# EM4100_cloner-revB.net
KiCad netlist of a schematic drawn in EAGLE
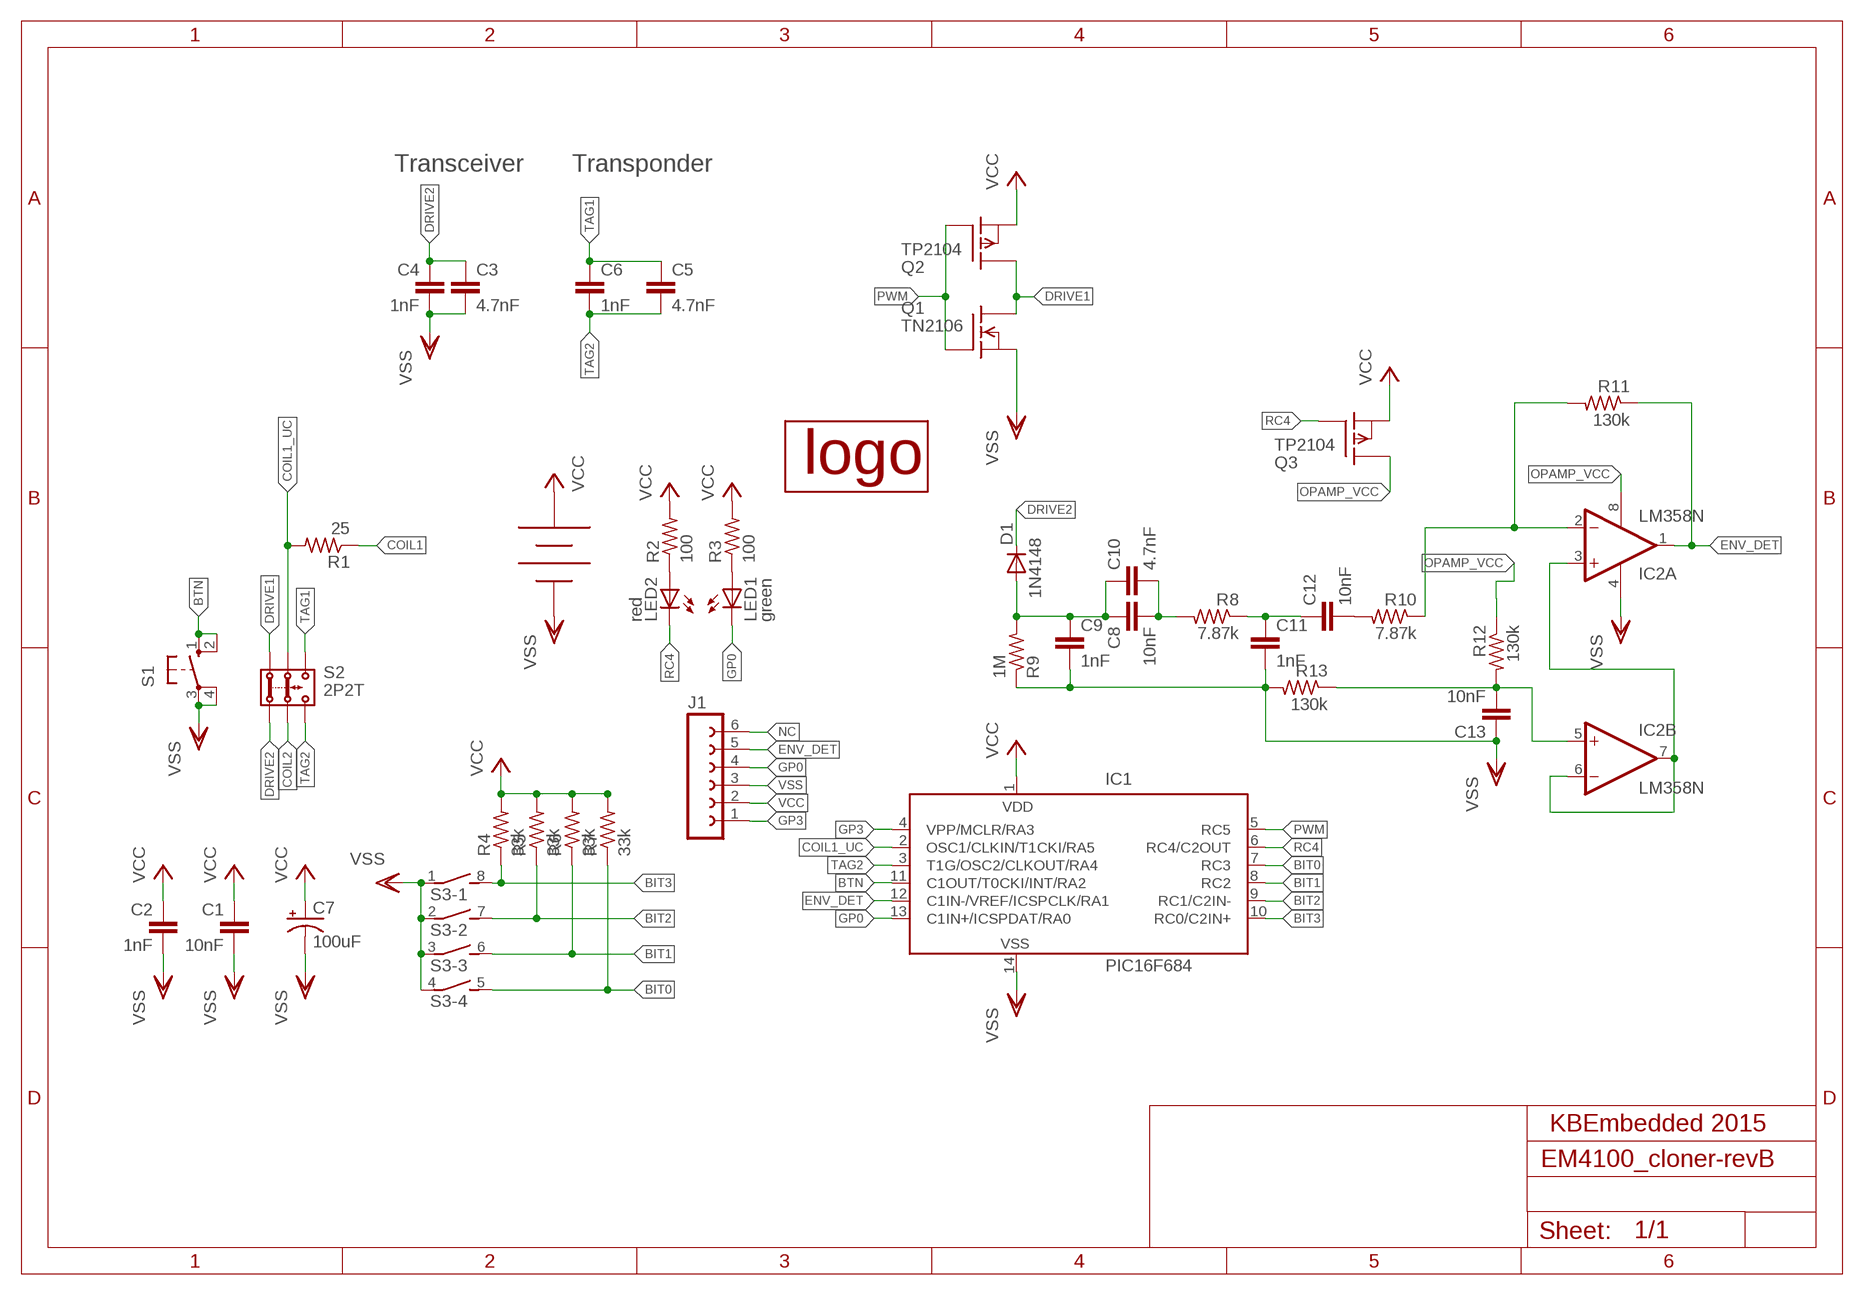
[diagram p0: schematic, sheet 1]

(export (version "E")
  (design (tool "Eeschema 10.0.6"))
  (components
    (comp (ref "BT1")
      (value "BAT-HLD-001-THM")
      (footprint "eagle-import:BAT-HLD-001-THM")
      (libsource (lib "eagle-import") (part "BAT-HLD-001-THM"))
    )
    (comp (ref "C1")
      (value "10nF")
      (footprint "eagle-import:C050-024X044")
      (libsource (lib "eagle-import") (part "C-EU050-024X044"))
    )
    (comp (ref "C2")
      (value "1nF")
      (footprint "eagle-import:C050-024X044")
      (libsource (lib "eagle-import") (part "C-EU050-024X044"))
    )
    (comp (ref "C3")
      (value "4.7nF")
      (footprint "eagle-import:C050-024X044")
      (libsource (lib "eagle-import") (part "C-EU050-024X044"))
    )
    (comp (ref "C4")
      (value "1nF")
      (footprint "eagle-import:C050-024X044")
      (libsource (lib "eagle-import") (part "C-EU050-024X044"))
    )
    (comp (ref "C5")
      (value "4.7nF")
      (footprint "eagle-import:C050-024X044")
      (libsource (lib "eagle-import") (part "C-EU050-024X044"))
    )
    (comp (ref "C6")
      (value "1nF")
      (footprint "eagle-import:C050-024X044")
      (libsource (lib "eagle-import") (part "C-EU050-024X044"))
    )
    (comp (ref "C7")
      (value "100uF")
      (footprint "eagle-import:E2,5-6E")
      (libsource (lib "eagle-import") (part "CPOL-USE2,5-6E"))
    )
    (comp (ref "C8")
      (value "10nF")
      (footprint "eagle-import:C050-024X044")
      (libsource (lib "eagle-import") (part "C-EU050-024X044"))
    )
    (comp (ref "C9")
      (value "1nF")
      (footprint "eagle-import:C050-024X044")
      (libsource (lib "eagle-import") (part "C-EU050-024X044"))
    )
    (comp (ref "C10")
      (value "4.7nF")
      (footprint "eagle-import:C050-024X044")
      (libsource (lib "eagle-import") (part "C-EU050-024X044"))
    )
    (comp (ref "C11")
      (value "1nF")
      (footprint "eagle-import:C050-024X044")
      (libsource (lib "eagle-import") (part "C-EU050-024X044"))
    )
    (comp (ref "C12")
      (value "10nF")
      (footprint "eagle-import:C050-024X044")
      (libsource (lib "eagle-import") (part "C-EU050-024X044"))
    )
    (comp (ref "C13")
      (value "10nF")
      (footprint "eagle-import:C050-024X044")
      (libsource (lib "eagle-import") (part "C-EU050-024X044"))
    )
    (comp (ref "D1")
      (value "1N4148")
      (footprint "eagle-import:D-5")
      (libsource (lib "eagle-import") (part "DIODE-D-5"))
    )
    (comp (ref "IC1")
      (value "PIC16F684")
      (footprint "eagle-import:DIL14")
      (fields (field (name "MF") "MICROCHIP") (field (name "MPN") "PIC16F636-I/P"))
      (libsource (lib "eagle-import") (part "PIC16F636P"))
    )
    (comp (ref "IC2")
      (value "LM358N")
      (footprint "eagle-import:DIL08")
      (libsource (lib "eagle-import") (part "LM358N"))
    )
    (comp (ref "J1")
      (value "FE06-1")
      (footprint "eagle-import:FE06")
      (libsource (lib "eagle-import") (part "FE06-1"))
    )
    (comp (ref "LED1")
      (value "green")
      (footprint "eagle-import:LED3MM")
      (libsource (lib "eagle-import") (part "LED3MM"))
    )
    (comp (ref "LED2")
      (value "red")
      (footprint "eagle-import:LED3MM")
      (libsource (lib "eagle-import") (part "LED3MM"))
    )
    (comp (ref "Q1")
      (value "TN2106")
      (footprint "eagle-import:TO-92")
      (libsource (lib "eagle-import") (part "TN0602N3"))
    )
    (comp (ref "Q2")
      (value "TP2104")
      (footprint "eagle-import:TO-92")
      (libsource (lib "eagle-import") (part "TP0602N3"))
    )
    (comp (ref "Q3")
      (value "TP2104")
      (footprint "eagle-import:TO-92")
      (libsource (lib "eagle-import") (part "TP0602N3"))
    )
    (comp (ref "R1")
      (value "25")
      (footprint "eagle-import:0204_7")
      (libsource (lib "eagle-import") (part "R-US_0204/7"))
    )
    (comp (ref "R2")
      (value "100")
      (footprint "eagle-import:0204_7")
      (libsource (lib "eagle-import") (part "R-US_0204/7"))
    )
    (comp (ref "R3")
      (value "100")
      (footprint "eagle-import:0204_7")
      (libsource (lib "eagle-import") (part "R-US_0204/7"))
    )
    (comp (ref "R4")
      (value "33k")
      (footprint "eagle-import:0204_7")
      (libsource (lib "eagle-import") (part "R-US_0204/7"))
    )
    (comp (ref "R5")
      (value "33k")
      (footprint "eagle-import:0204_7")
      (libsource (lib "eagle-import") (part "R-US_0204/7"))
    )
    (comp (ref "R6")
      (value "33k")
      (footprint "eagle-import:0204_7")
      (libsource (lib "eagle-import") (part "R-US_0204/7"))
    )
    (comp (ref "R7")
      (value "33k")
      (footprint "eagle-import:0204_7")
      (libsource (lib "eagle-import") (part "R-US_0204/7"))
    )
    (comp (ref "R8")
      (value "7.87k")
      (footprint "eagle-import:0204_7")
      (libsource (lib "eagle-import") (part "R-US_0204/7"))
    )
    (comp (ref "R9")
      (value "1M")
      (footprint "eagle-import:0204_7")
      (libsource (lib "eagle-import") (part "R-US_0204/7"))
    )
    (comp (ref "R10")
      (value "7.87k")
      (footprint "eagle-import:0204_7")
      (libsource (lib "eagle-import") (part "R-US_0204/7"))
    )
    (comp (ref "R11")
      (value "130k")
      (footprint "eagle-import:0204_7")
      (libsource (lib "eagle-import") (part "R-US_0204/7"))
    )
    (comp (ref "R12")
      (value "130k")
      (footprint "eagle-import:0204_7")
      (libsource (lib "eagle-import") (part "R-US_0204/7"))
    )
    (comp (ref "R13")
      (value "130k")
      (footprint "eagle-import:0204_7")
      (libsource (lib "eagle-import") (part "R-US_0204/7"))
    )
    (comp (ref "S1")
      (value "10-XX")
      (footprint "eagle-import:B3F-10XX")
      (fields (field (name "MPN") "B3F-1000"))
      (libsource (lib "eagle-import") (part "10-XX"))
    )
    (comp (ref "S2")
      (value "2P2T")
      (footprint "eagle-import:2P2T")
      (libsource (lib "eagle-import") (part "2P2T"))
    )
    (comp (ref "S3")
      (value "DIP04S")
      (footprint "eagle-import:DIP04S")
      (libsource (lib "eagle-import") (part "DIP04S"))
    )
    (comp (ref "U$1")
      (value "KBELOGO-SILK")
      (footprint "eagle-import:KBELOGO-SILK")
      (libsource (lib "eagle-import") (part "KBELOGO-SILK"))
    )
  )
  (nets
    (net (code "1") (name "BIT0") (class "Default")
      (node (ref "IC1") (pin "7") (pinfunction "RC3_7") (pintype "bidirectional"))
      (node (ref "R7") (pin "1") (pinfunction "1_1") (pintype "passive"))
      (node (ref "S3") (pin "5") (pinfunction "2_5") (pintype "passive"))
    )
    (net (code "2") (name "BIT1") (class "Default")
      (node (ref "IC1") (pin "8") (pinfunction "RC2_8") (pintype "bidirectional"))
      (node (ref "R6") (pin "1") (pinfunction "1_1") (pintype "passive"))
      (node (ref "S3") (pin "6") (pinfunction "2_6") (pintype "passive"))
    )
    (net (code "3") (name "BIT2") (class "Default")
      (node (ref "IC1") (pin "9") (pinfunction "RC1/C2IN-_9") (pintype "bidirectional"))
      (node (ref "R5") (pin "1") (pinfunction "1_1") (pintype "passive"))
      (node (ref "S3") (pin "7") (pinfunction "2_7") (pintype "passive"))
    )
    (net (code "4") (name "BIT3") (class "Default")
      (node (ref "IC1") (pin "10") (pinfunction "RC0/C2IN+_10") (pintype "bidirectional"))
      (node (ref "R4") (pin "1") (pinfunction "1_1") (pintype "passive"))
      (node (ref "S3") (pin "8") (pinfunction "2_8") (pintype "passive"))
    )
    (net (code "5") (name "BTN") (class "Default")
      (node (ref "IC1") (pin "11") (pinfunction "C1OUT/T0CKI/INT/RA2_11") (pintype "bidirectional"))
      (node (ref "S1") (pin "1") (pinfunction "S_1") (pintype "passive"))
      (node (ref "S1") (pin "2") (pinfunction "S1_2") (pintype "passive"))
    )
    (net (code "6") (name "COIL1") (class "Default")
      (node (ref "R1") (pin "1") (pinfunction "1_1") (pintype "passive"))
    )
    (net (code "7") (name "COIL1_UC") (class "Default")
      (node (ref "IC1") (pin "2") (pinfunction "OSC1/CLKIN/T1CKI/RA5_2") (pintype "bidirectional"))
      (node (ref "R1") (pin "2") (pinfunction "2_2") (pintype "passive"))
      (node (ref "S2") (pin "2.1") (pinfunction "2.1_2.1") (pintype "passive"))
    )
    (net (code "8") (name "COIL2") (class "Default")
      (node (ref "S2") (pin "2.2") (pinfunction "2.2_2.2") (pintype "passive"))
    )
    (net (code "9") (name "DRIVE1") (class "Default")
      (node (ref "Q1") (pin "3") (pinfunction "D_3") (pintype "passive"))
      (node (ref "Q2") (pin "3") (pinfunction "D_3") (pintype "passive"))
      (node (ref "S2") (pin "1.1") (pinfunction "1.1_1.1") (pintype "passive"))
    )
    (net (code "10") (name "DRIVE2") (class "Default")
      (node (ref "C3") (pin "1") (pinfunction "1_1") (pintype "passive"))
      (node (ref "C4") (pin "1") (pinfunction "1_1") (pintype "passive"))
      (node (ref "D1") (pin "C") (pinfunction "C_C") (pintype "passive"))
      (node (ref "S2") (pin "1.2") (pinfunction "1.2_1.2") (pintype "passive"))
    )
    (net (code "11") (name "ENV_DET") (class "Default")
      (node (ref "IC1") (pin "12") (pinfunction "C1IN-/VREF/ICSPCLK/RA1_12") (pintype "bidirectional"))
      (node (ref "IC2") (pin "1") (pinfunction "OUT_1") (pintype "output"))
      (node (ref "J1") (pin "5") (pinfunction "5_5") (pintype "passive"))
      (node (ref "R11") (pin "1") (pinfunction "1_1") (pintype "passive"))
    )
    (net (code "12") (name "GP0") (class "Default")
      (node (ref "IC1") (pin "13") (pinfunction "C1IN+/ICSPDAT/RA0_13") (pintype "bidirectional"))
      (node (ref "J1") (pin "4") (pinfunction "4_4") (pintype "passive"))
      (node (ref "LED1") (pin "K") (pinfunction "C_K") (pintype "passive"))
    )
    (net (code "13") (name "GP3") (class "Default")
      (node (ref "IC1") (pin "4") (pinfunction "VPP/MCLR/RA3_4") (pintype "input"))
      (node (ref "J1") (pin "1") (pinfunction "1_1") (pintype "passive"))
    )
    (net (code "14") (name "NC") (class "Default")
      (node (ref "J1") (pin "6") (pinfunction "6_6") (pintype "passive"))
    )
    (net (code "15") (name "Net-(C10-Pad1)") (class "Default")
      (node (ref "C10") (pin "1") (pinfunction "1_1") (pintype "passive"))
      (node (ref "C8") (pin "1") (pinfunction "1_1") (pintype "passive"))
      (node (ref "C9") (pin "1") (pinfunction "1_1") (pintype "passive"))
      (node (ref "D1") (pin "A") (pinfunction "A_A") (pintype "passive"))
      (node (ref "R9") (pin "2") (pinfunction "2_2") (pintype "passive"))
    )
    (net (code "16") (name "Net-(C10-Pad2)") (class "Default")
      (node (ref "C10") (pin "2") (pinfunction "2_2") (pintype "passive"))
      (node (ref "C8") (pin "2") (pinfunction "2_2") (pintype "passive"))
      (node (ref "R8") (pin "2") (pinfunction "2_2") (pintype "passive"))
    )
    (net (code "17") (name "Net-(C11-Pad1)") (class "Default")
      (node (ref "C11") (pin "1") (pinfunction "1_1") (pintype "passive"))
      (node (ref "C12") (pin "1") (pinfunction "1_1") (pintype "passive"))
      (node (ref "R8") (pin "1") (pinfunction "1_1") (pintype "passive"))
    )
    (net (code "18") (name "Net-(C12-Pad2)") (class "Default")
      (node (ref "C12") (pin "2") (pinfunction "2_2") (pintype "passive"))
      (node (ref "R10") (pin "2") (pinfunction "2_2") (pintype "passive"))
    )
    (net (code "19") (name "Net-(IC2A-+IN)") (class "Default")
      (node (ref "IC2") (pin "3") (pinfunction "+IN_3") (pintype "input"))
      (node (ref "IC2") (pin "6") (pinfunction "-IN_6") (pintype "input"))
      (node (ref "IC2") (pin "7") (pinfunction "OUT_7") (pintype "output"))
    )
    (net (code "20") (name "Net-(IC2A--IN)") (class "Default")
      (node (ref "IC2") (pin "2") (pinfunction "-IN_2") (pintype "input"))
      (node (ref "R10") (pin "1") (pinfunction "1_1") (pintype "passive"))
      (node (ref "R11") (pin "2") (pinfunction "2_2") (pintype "passive"))
    )
    (net (code "21") (name "Net-(IC2B-+IN)") (class "Default")
      (node (ref "C13") (pin "2") (pinfunction "2_2") (pintype "passive"))
      (node (ref "IC2") (pin "5") (pinfunction "+IN_5") (pintype "input"))
      (node (ref "R12") (pin "2") (pinfunction "2_2") (pintype "passive"))
      (node (ref "R13") (pin "1") (pinfunction "1_1") (pintype "passive"))
    )
    (net (code "22") (name "Net-(LED1-PadA)") (class "Default")
      (node (ref "LED1") (pin "A") (pinfunction "A_A") (pintype "passive"))
      (node (ref "R3") (pin "1") (pinfunction "1_1") (pintype "passive"))
    )
    (net (code "23") (name "Net-(LED2-PadA)") (class "Default")
      (node (ref "LED2") (pin "A") (pinfunction "A_A") (pintype "passive"))
      (node (ref "R2") (pin "1") (pinfunction "1_1") (pintype "passive"))
    )
    (net (code "24") (name "OPAMP_VCC") (class "Default")
      (node (ref "IC2") (pin "8") (pinfunction "V+_8") (pintype "power_in"))
      (node (ref "Q3") (pin "3") (pinfunction "D_3") (pintype "passive"))
      (node (ref "R12") (pin "1") (pinfunction "1_1") (pintype "passive"))
    )
    (net (code "25") (name "PWM") (class "Default")
      (node (ref "IC1") (pin "5") (pinfunction "RC5_5") (pintype "bidirectional"))
      (node (ref "Q1") (pin "2") (pinfunction "G_2") (pintype "passive"))
      (node (ref "Q2") (pin "2") (pinfunction "G_2") (pintype "passive"))
    )
    (net (code "26") (name "RC4") (class "Default")
      (node (ref "IC1") (pin "6") (pinfunction "RC4/C2OUT_6") (pintype "bidirectional"))
      (node (ref "LED2") (pin "K") (pinfunction "C_K") (pintype "passive"))
      (node (ref "Q3") (pin "2") (pinfunction "G_2") (pintype "passive"))
    )
    (net (code "27") (name "TAG1") (class "Default")
      (node (ref "C5") (pin "1") (pinfunction "1_1") (pintype "passive"))
      (node (ref "C6") (pin "1") (pinfunction "1_1") (pintype "passive"))
      (node (ref "S2") (pin "3.1") (pinfunction "3.1_3.1") (pintype "passive"))
    )
    (net (code "28") (name "TAG2") (class "Default")
      (node (ref "C5") (pin "2") (pinfunction "2_2") (pintype "passive"))
      (node (ref "C6") (pin "2") (pinfunction "2_2") (pintype "passive"))
      (node (ref "IC1") (pin "3") (pinfunction "T1G/OSC2/CLKOUT/RA4_3") (pintype "bidirectional"))
      (node (ref "S2") (pin "3.2") (pinfunction "3.2_3.2") (pintype "passive"))
    )
    (net (code "29") (name "VCC") (class "Default")
      (node (ref "BT1") (pin "+@0") (pinfunction "VCC_+@0") (pintype "bidirectional"))
      (node (ref "BT1") (pin "+@1") (pinfunction "VCC_+@1") (pintype "bidirectional"))
      (node (ref "BT1") (pin "+@2") (pinfunction "VCC_+@2") (pintype "bidirectional"))
      (node (ref "BT1") (pin "+@3") (pinfunction "VCC_+@3") (pintype "bidirectional"))
      (node (ref "C1") (pin "1") (pinfunction "1_1") (pintype "passive"))
      (node (ref "C2") (pin "1") (pinfunction "1_1") (pintype "passive"))
      (node (ref "C7") (pin "+") (pinfunction "+_+") (pintype "passive"))
      (node (ref "IC1") (pin "1") (pinfunction "VDD_1") (pintype "power_in"))
      (node (ref "J1") (pin "2") (pinfunction "2_2") (pintype "passive"))
      (node (ref "Q2") (pin "1") (pinfunction "S_1") (pintype "passive"))
      (node (ref "Q3") (pin "1") (pinfunction "S_1") (pintype "passive"))
      (node (ref "R2") (pin "2") (pinfunction "2_2") (pintype "passive"))
      (node (ref "R3") (pin "2") (pinfunction "2_2") (pintype "passive"))
      (node (ref "R4") (pin "2") (pinfunction "2_2") (pintype "passive"))
      (node (ref "R5") (pin "2") (pinfunction "2_2") (pintype "passive"))
      (node (ref "R6") (pin "2") (pinfunction "2_2") (pintype "passive"))
      (node (ref "R7") (pin "2") (pinfunction "2_2") (pintype "passive"))
    )
    (net (code "30") (name "VSS") (class "Default")
      (node (ref "BT1") (pin "-") (pinfunction "VSS_-") (pintype "bidirectional"))
      (node (ref "C1") (pin "2") (pinfunction "2_2") (pintype "passive"))
      (node (ref "C11") (pin "2") (pinfunction "2_2") (pintype "passive"))
      (node (ref "C13") (pin "1") (pinfunction "1_1") (pintype "passive"))
      (node (ref "C2") (pin "2") (pinfunction "2_2") (pintype "passive"))
      (node (ref "C3") (pin "2") (pinfunction "2_2") (pintype "passive"))
      (node (ref "C4") (pin "2") (pinfunction "2_2") (pintype "passive"))
      (node (ref "C7") (pin "-") (pinfunction "-_-") (pintype "passive"))
      (node (ref "C9") (pin "2") (pinfunction "2_2") (pintype "passive"))
      (node (ref "IC1") (pin "14") (pinfunction "VSS_14") (pintype "power_in"))
      (node (ref "IC2") (pin "4") (pinfunction "V-_4") (pintype "power_in"))
      (node (ref "J1") (pin "3") (pinfunction "3_3") (pintype "passive"))
      (node (ref "Q1") (pin "1") (pinfunction "S_1") (pintype "passive"))
      (node (ref "R13") (pin "2") (pinfunction "2_2") (pintype "passive"))
      (node (ref "R9") (pin "1") (pinfunction "1_1") (pintype "passive"))
      (node (ref "S1") (pin "3") (pinfunction "P_3") (pintype "passive"))
      (node (ref "S1") (pin "4") (pinfunction "P1_4") (pintype "passive"))
      (node (ref "S3") (pin "1") (pinfunction "1_1") (pintype "passive"))
      (node (ref "S3") (pin "2") (pinfunction "1_2") (pintype "passive"))
      (node (ref "S3") (pin "3") (pinfunction "1_3") (pintype "passive"))
      (node (ref "S3") (pin "4") (pinfunction "1_4") (pintype "passive"))
    )
  )
)
